# filter.net
KiCad netlist of a schematic drawn in EasyEDA Pro
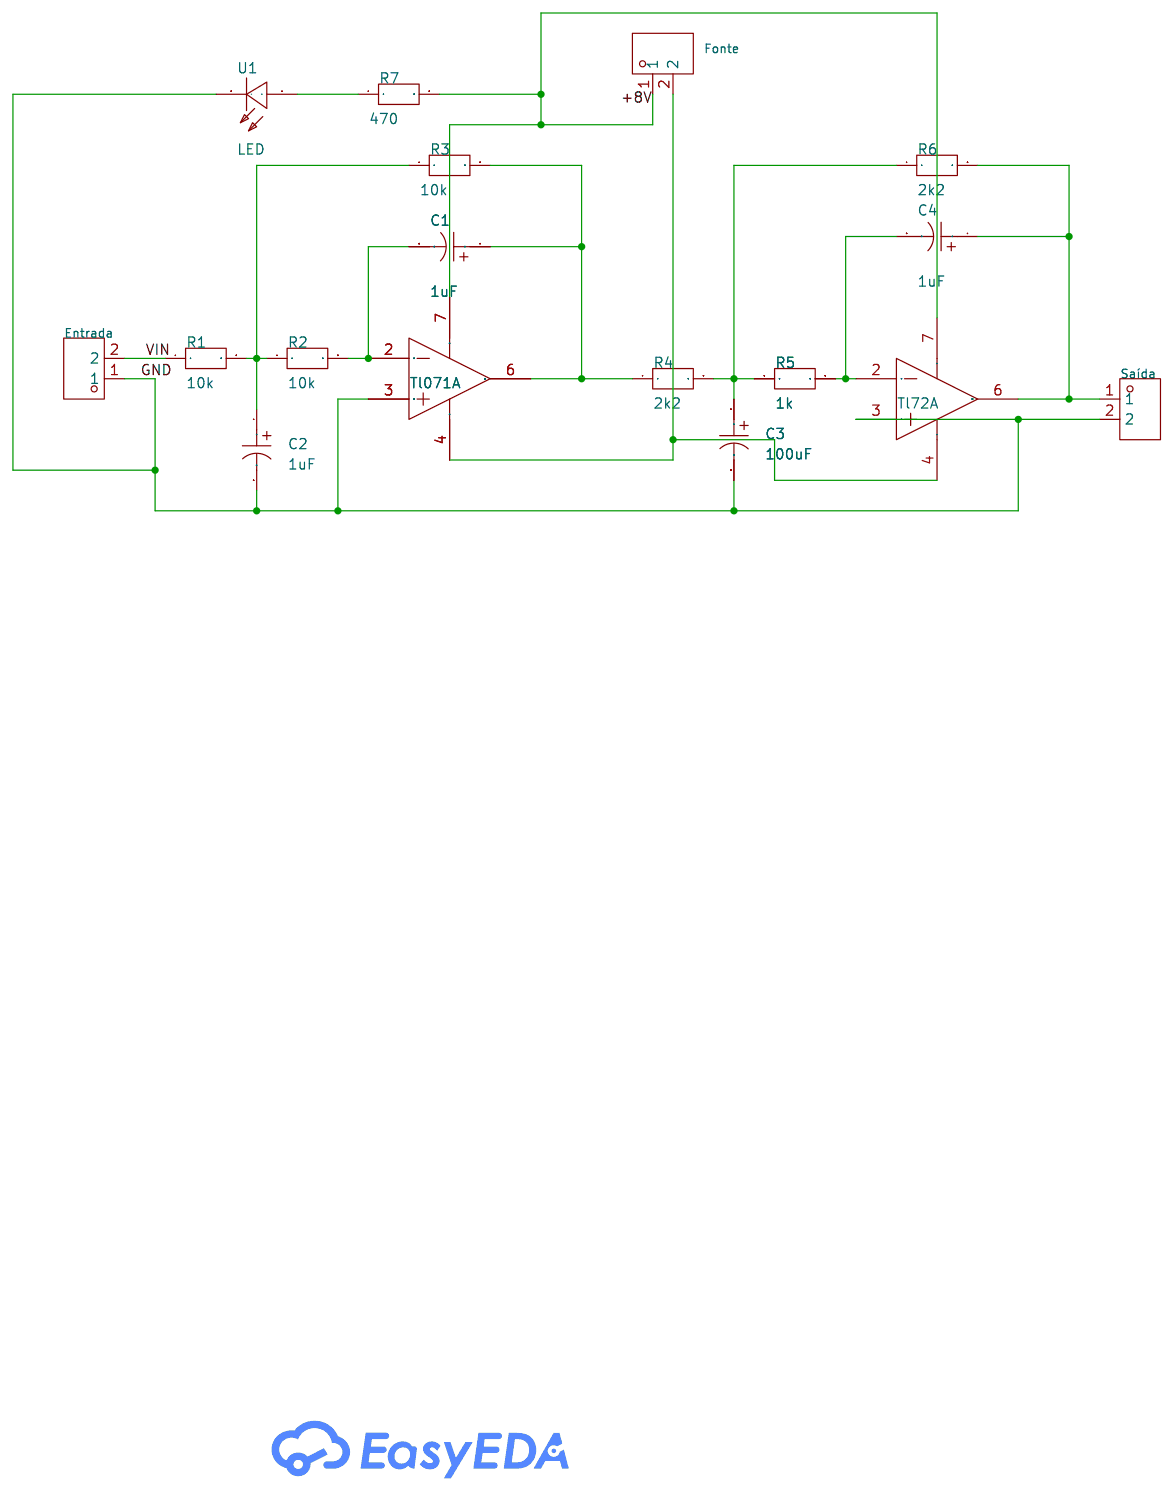
[diagram p0: schematic sheet]

(export (version "E")
  (design (tool "Eeschema 10.0.6"))
  (components
    (comp (ref "C1")
      (value "1uF")
      (footprint "easyedapro:CAP-TH_BD5.0-P2.00-D0.5-FD-1")
      (fields (field (name "Manufacturer Part") "50V1uF CD110") (field (name "Manufacturer") "HRK(鸿瑞凯电子)"))
      (libsource (lib "easyedapro") (part "50V1UF CD110"))
    )
    (comp (ref "C2")
      (value "1uF")
      (footprint "easyedapro:CAP-TH_BD5.0-P2.00-D0.5-FD-1")
      (fields (field (name "Manufacturer Part") "50V1uF CD110") (field (name "Manufacturer") "HRK(鸿瑞凯电子)"))
      (libsource (lib "easyedapro") (part "50V1UF CD110"))
    )
    (comp (ref "C3")
      (value "100uF")
      (footprint "easyedapro:CAP-TH_BD5.0-P2.00-D0.5-FD-1")
      (fields (field (name "Manufacturer Part") "50V1uF CD110") (field (name "Manufacturer") "HRK(鸿瑞凯电子)"))
      (libsource (lib "easyedapro") (part "50V1UF CD110"))
    )
    (comp (ref "C4")
      (value "1uF")
      (footprint "easyedapro:CAP-TH_BD5.0-P2.00-D0.5-FD-1")
      (fields (field (name "Manufacturer Part") "50V1uF CD110") (field (name "Manufacturer") "HRK(鸿瑞凯电子)"))
      (libsource (lib "easyedapro") (part "50V1UF CD110"))
    )
    (comp (ref "Entrada")
      (value "KF128L-5.08-2P")
      (footprint "easyedapro:CONN-TH_P5.08_KF128L-5.08-2P")
      (fields (field (name "Manufacturer") "KEFA(科发)"))
      (libsource (lib "easyedapro") (part "KF128L-5.08-2P"))
    )
    (comp (ref "Fonte")
      (value "KF128L-5.08-2P")
      (footprint "easyedapro:CONN-TH_P5.08_KF128L-5.08-2P")
      (fields (field (name "Manufacturer") "KEFA(科发)"))
      (libsource (lib "easyedapro") (part "KF128L-5.08-2P"))
    )
    (comp (ref "R1")
      (value "10k")
      (footprint "easyedapro:RES-TH_BD2.3-L6.5-P10.50-D0.5")
      (fields (field (name "Manufacturer Part") "MF1/4W-1KΩ±1%T52") (field (name "Manufacturer") "华星机电"))
      (libsource (lib "easyedapro") (part "MF1/4W-1KΩ±1%T52"))
    )
    (comp (ref "R2")
      (value "10k")
      (footprint "easyedapro:RES-TH_BD2.3-L6.5-P10.50-D0.5")
      (fields (field (name "Manufacturer Part") "MF1/4W-1KΩ±1%T52") (field (name "Manufacturer") "华星机电"))
      (libsource (lib "easyedapro") (part "MF1/4W-1KΩ±1%T52"))
    )
    (comp (ref "R3")
      (value "10k")
      (footprint "easyedapro:RES-TH_BD2.3-L6.5-P10.50-D0.5")
      (fields (field (name "Manufacturer Part") "MF1/4W-1KΩ±1%T52") (field (name "Manufacturer") "华星机电"))
      (libsource (lib "easyedapro") (part "MF1/4W-1KΩ±1%T52"))
    )
    (comp (ref "R4")
      (value "2k2")
      (footprint "easyedapro:RES-TH_BD2.3-L6.5-P10.50-D0.5")
      (fields (field (name "Manufacturer Part") "MF1/4W-1KΩ±1%T52") (field (name "Manufacturer") "华星机电"))
      (libsource (lib "easyedapro") (part "MF1/4W-1KΩ±1%T52"))
    )
    (comp (ref "R5")
      (value "1k")
      (footprint "easyedapro:RES-TH_BD2.3-L6.5-P10.50-D0.5")
      (fields (field (name "Manufacturer Part") "MF1/4W-1KΩ±1%T52") (field (name "Manufacturer") "华星机电"))
      (libsource (lib "easyedapro") (part "MF1/4W-1KΩ±1%T52"))
    )
    (comp (ref "R6")
      (value "2k2")
      (footprint "easyedapro:RES-TH_BD2.3-L6.5-P10.50-D0.5")
      (fields (field (name "Manufacturer Part") "MF1/4W-1KΩ±1%T52") (field (name "Manufacturer") "华星机电"))
      (libsource (lib "easyedapro") (part "MF1/4W-1KΩ±1%T52"))
    )
    (comp (ref "R7")
      (value "470")
      (footprint "easyedapro:RES-TH_BD2.3-L6.5-P10.50-D0.5")
      (fields (field (name "Manufacturer Part") "MF1/4W-1KΩ±1%T52") (field (name "Manufacturer") "华星机电"))
      (libsource (lib "easyedapro") (part "MF1/4W-1KΩ±1%T52"))
    )
    (comp (ref "Saída")
      (value "KF128L-5.08-2P")
      (footprint "easyedapro:CONN-TH_P5.08_KF128L-5.08-2P")
      (fields (field (name "Manufacturer") "KEFA(科发)"))
      (libsource (lib "easyedapro") (part "KF128L-5.08-2P"))
    )
    (comp (ref "Tl071")
      (value "CA3140N-TD")
      (footprint "easyedapro:DIP-8_L9.3-W6.4-P2.54-LS7.6-BL-1")
      (fields (field (name "Manufacturer") "TDSEMIC(拓电半导体)"))
      (libsource (lib "easyedapro") (part "CA3140N-TD"))
    )
    (comp (ref "Tl72")
      (value "CA3140N-TD")
      (footprint "easyedapro:DIP-8_L9.3-W6.4-P2.54-LS7.6-BL-1")
      (fields (field (name "Manufacturer") "TDSEMIC(拓电半导体)"))
      (libsource (lib "easyedapro") (part "CA3140N-TD"))
    )
    (comp (ref "U1")
      (value "LED")
      (footprint "easyedapro:LED-TH_BD4.0-P2.54-FD_RED")
      (libsource (lib "easyedapro") (part "LED_C9900015665"))
    )
  )
  (nets
    (net (code "1") (name "/+8V") (class "Default")
      (node (ref "Fonte") (pin "1") (pinfunction "1_1") (pintype "input"))
      (node (ref "R7") (pin "2") (pinfunction "2_2") (pintype "unspecified"))
      (node (ref "Tl071") (pin "7") (pinfunction "V+_7") (pintype "unspecified"))
      (node (ref "Tl72") (pin "7") (pinfunction "V+_7") (pintype "unspecified"))
    )
    (net (code "2") (name "/GND") (class "Default")
      (node (ref "C2") (pin "2") (pinfunction "2_2") (pintype "input"))
      (node (ref "C3") (pin "2") (pinfunction "2_2") (pintype "input"))
      (node (ref "Entrada") (pin "1") (pinfunction "1_1") (pintype "input"))
      (node (ref "Saída") (pin "2") (pinfunction "2_2") (pintype "input"))
      (node (ref "Tl071") (pin "3") (pinfunction "IN+_3") (pintype "unspecified"))
      (node (ref "Tl72") (pin "3") (pinfunction "IN+_3") (pintype "unspecified"))
      (node (ref "U1") (pin "2") (pinfunction "-_2") (pintype "unspecified"))
    )
    (net (code "3") (name "/VIN") (class "Default")
      (node (ref "Entrada") (pin "2") (pinfunction "2_2") (pintype "input"))
      (node (ref "R1") (pin "1") (pinfunction "1_1") (pintype "unspecified"))
    )
    (net (code "4") (name "Net-(C2-Pad1)") (class "Default")
      (node (ref "C2") (pin "1") (pinfunction "1_1") (pintype "input"))
      (node (ref "R1") (pin "2") (pinfunction "2_2") (pintype "unspecified"))
      (node (ref "R2") (pin "1") (pinfunction "1_1") (pintype "unspecified"))
      (node (ref "R3") (pin "1") (pinfunction "1_1") (pintype "unspecified"))
    )
    (net (code "5") (name "Net-(C3-Pad1)") (class "Default")
      (node (ref "C3") (pin "1") (pinfunction "1_1") (pintype "input"))
      (node (ref "R4") (pin "2") (pinfunction "2_2") (pintype "unspecified"))
      (node (ref "R5") (pin "1") (pinfunction "1_1") (pintype "unspecified"))
      (node (ref "R6") (pin "1") (pinfunction "1_1") (pintype "unspecified"))
    )
    (net (code "6") (name "Net-(Tl071A-IN-)") (class "Default")
      (node (ref "C1") (pin "2") (pinfunction "2_2") (pintype "input"))
      (node (ref "R2") (pin "2") (pinfunction "2_2") (pintype "unspecified"))
      (node (ref "Tl071") (pin "2") (pinfunction "IN-_2") (pintype "unspecified"))
    )
    (net (code "7") (name "Net-(Tl071A-OUT)") (class "Default")
      (node (ref "C1") (pin "1") (pinfunction "1_1") (pintype "input"))
      (node (ref "R3") (pin "2") (pinfunction "2_2") (pintype "unspecified"))
      (node (ref "R4") (pin "1") (pinfunction "1_1") (pintype "unspecified"))
      (node (ref "Tl071") (pin "6") (pinfunction "OUT_6") (pintype "output"))
    )
    (net (code "8") (name "Net-(Tl071A-V-)") (class "Default")
      (node (ref "Fonte") (pin "2") (pinfunction "2_2") (pintype "input"))
      (node (ref "Tl071") (pin "4") (pinfunction "V-_4") (pintype "unspecified"))
      (node (ref "Tl72") (pin "4") (pinfunction "V-_4") (pintype "unspecified"))
    )
    (net (code "9") (name "Net-(Tl72A-IN-)") (class "Default")
      (node (ref "C4") (pin "2") (pinfunction "2_2") (pintype "input"))
      (node (ref "R5") (pin "2") (pinfunction "2_2") (pintype "unspecified"))
      (node (ref "Tl72") (pin "2") (pinfunction "IN-_2") (pintype "unspecified"))
    )
    (net (code "10") (name "Net-(Tl72A-OUT)") (class "Default")
      (node (ref "C4") (pin "1") (pinfunction "1_1") (pintype "input"))
      (node (ref "R6") (pin "2") (pinfunction "2_2") (pintype "unspecified"))
      (node (ref "Saída") (pin "1") (pinfunction "1_1") (pintype "input"))
      (node (ref "Tl72") (pin "6") (pinfunction "OUT_6") (pintype "output"))
    )
    (net (code "11") (name "Net-(U1-+)") (class "Default")
      (node (ref "R7") (pin "1") (pinfunction "1_1") (pintype "unspecified"))
      (node (ref "U1") (pin "1") (pinfunction "+_1") (pintype "unspecified"))
    )
  )
)
